# OPT3001.net
KiCad netlist of a schematic drawn in EAGLE
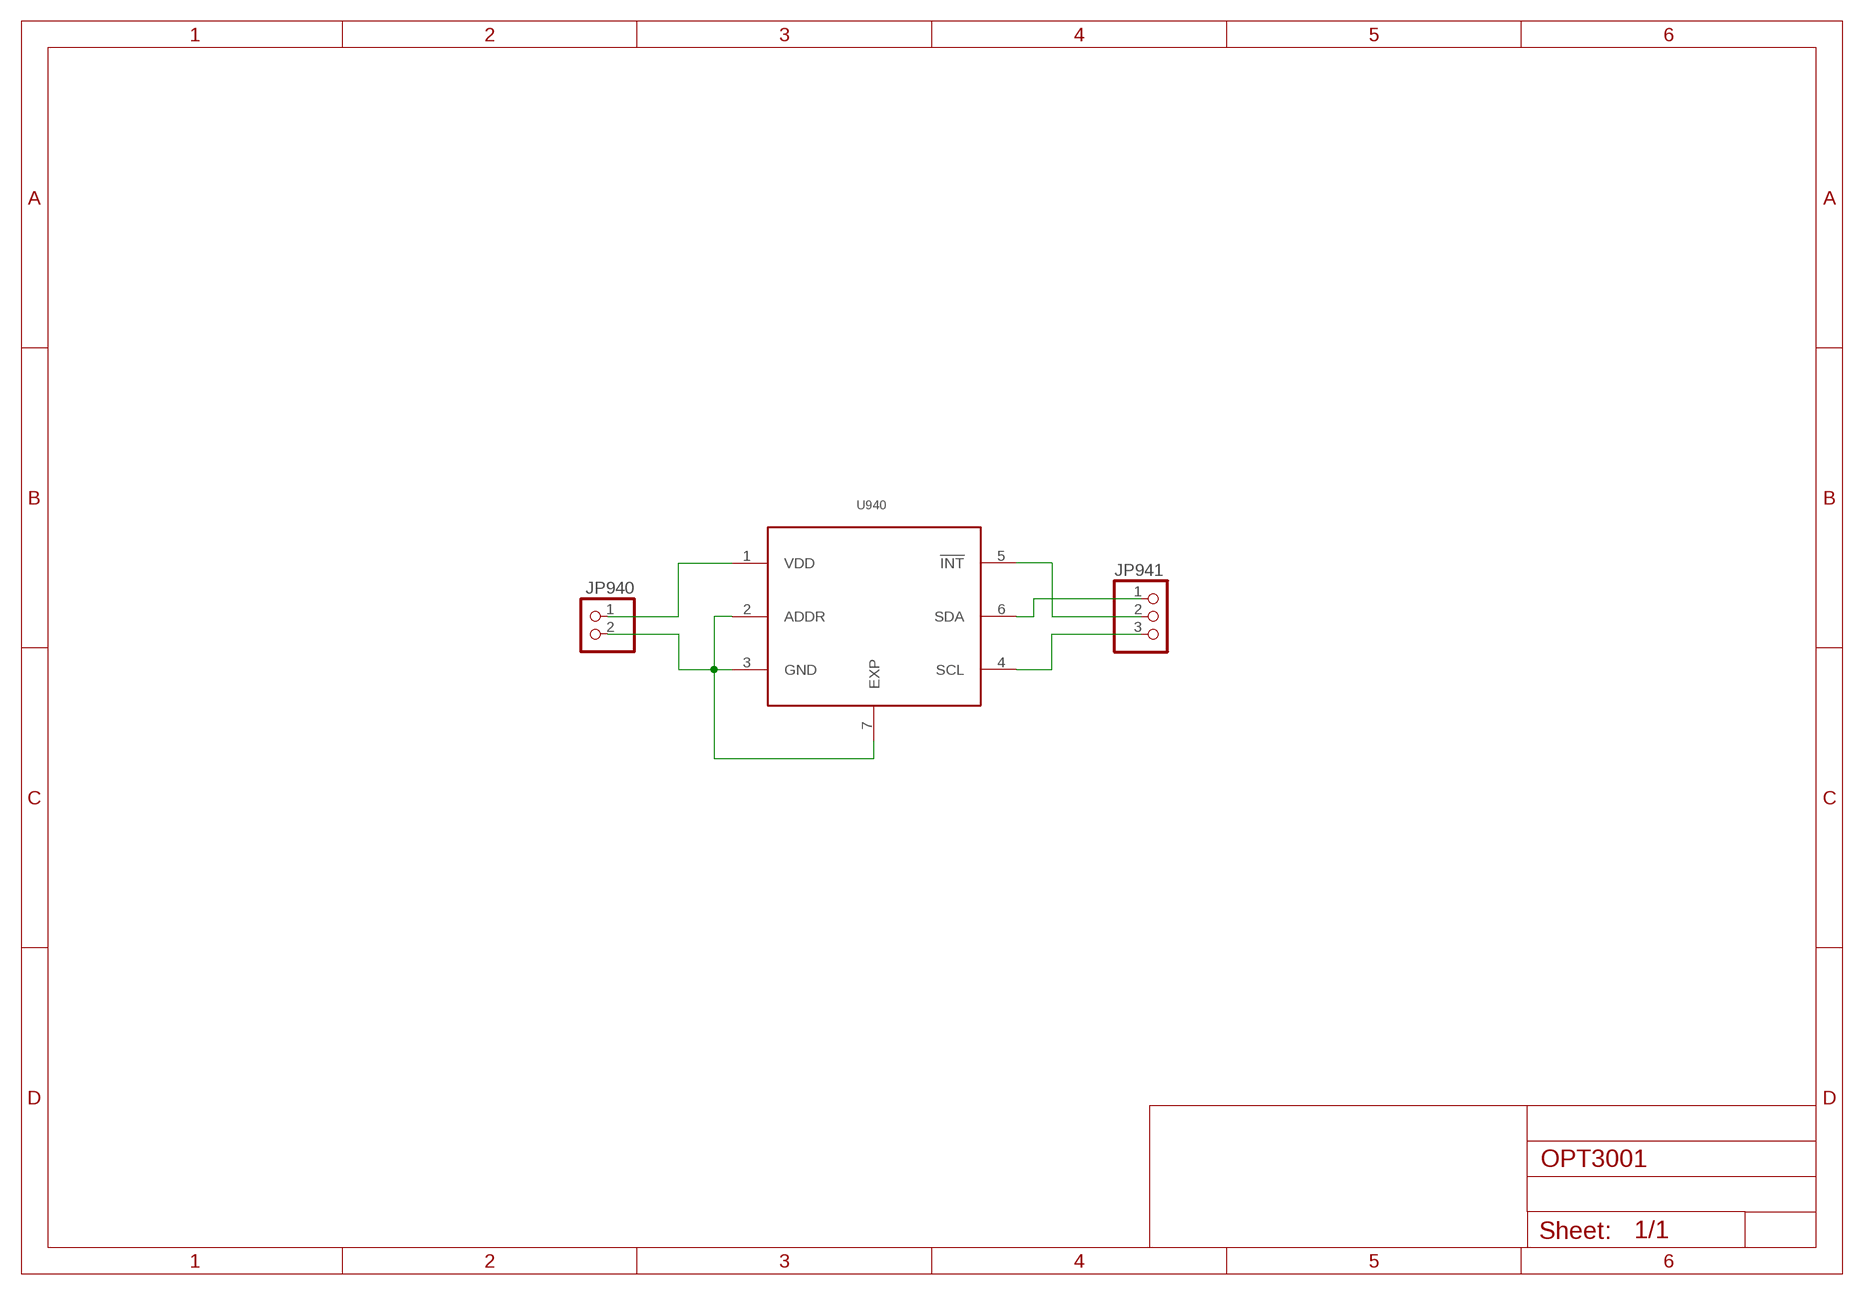
[diagram p0: schematic, sheet 1]

(export (version "E")
  (design (tool "Eeschema 10.0.6"))
  (components
    (comp (ref "JP940")
      (value "PINHD-1X2")
      (footprint "eagle-import:1X02")
      (libsource (lib "eagle-import") (part "PINHD-1X2"))
    )
    (comp (ref "JP941")
      (value "PINHD-1X3")
      (footprint "eagle-import:1X03")
      (libsource (lib "eagle-import") (part "PINHD-1X3"))
    )
    (comp (ref "U940")
      (value "OPT3001")
      (footprint "eagle-import:SON65P200X200X65-7T66X136N")
      (libsource (lib "eagle-import") (part "OPT3001"))
    )
  )
  (nets
    (net (code "1") (name "Net-(U940-ADDR)") (class "Default")
      (node (ref "JP940") (pin "2") (pinfunction "2_2") (pintype "passive"))
      (node (ref "U940") (pin "2") (pinfunction "ADDR_2") (pintype "bidirectional"))
      (node (ref "U940") (pin "3") (pinfunction "GND_3") (pintype "bidirectional"))
      (node (ref "U940") (pin "7") (pinfunction "EXP_7") (pintype "bidirectional"))
    )
    (net (code "2") (name "Net-(U940-SCL)") (class "Default")
      (node (ref "JP941") (pin "3") (pinfunction "3_3") (pintype "passive"))
      (node (ref "U940") (pin "4") (pinfunction "SCL_4") (pintype "bidirectional"))
    )
    (net (code "3") (name "Net-(U940-SDA)") (class "Default")
      (node (ref "JP941") (pin "1") (pinfunction "1_1") (pintype "passive"))
      (node (ref "U940") (pin "6") (pinfunction "SDA_6") (pintype "bidirectional"))
    )
    (net (code "4") (name "Net-(U940-VDD)") (class "Default")
      (node (ref "JP940") (pin "1") (pinfunction "1_1") (pintype "passive"))
      (node (ref "U940") (pin "1") (pinfunction "VDD_1") (pintype "bidirectional"))
    )
    (net (code "5") (name "Net-(U940-~{INT})") (class "Default")
      (node (ref "JP941") (pin "2") (pinfunction "2_2") (pintype "passive"))
      (node (ref "U940") (pin "5") (pinfunction "~{INT}_5") (pintype "bidirectional"))
    )
  )
)
